# battery-nurse-1-2-1.net
KiCad netlist of a schematic drawn in EAGLE
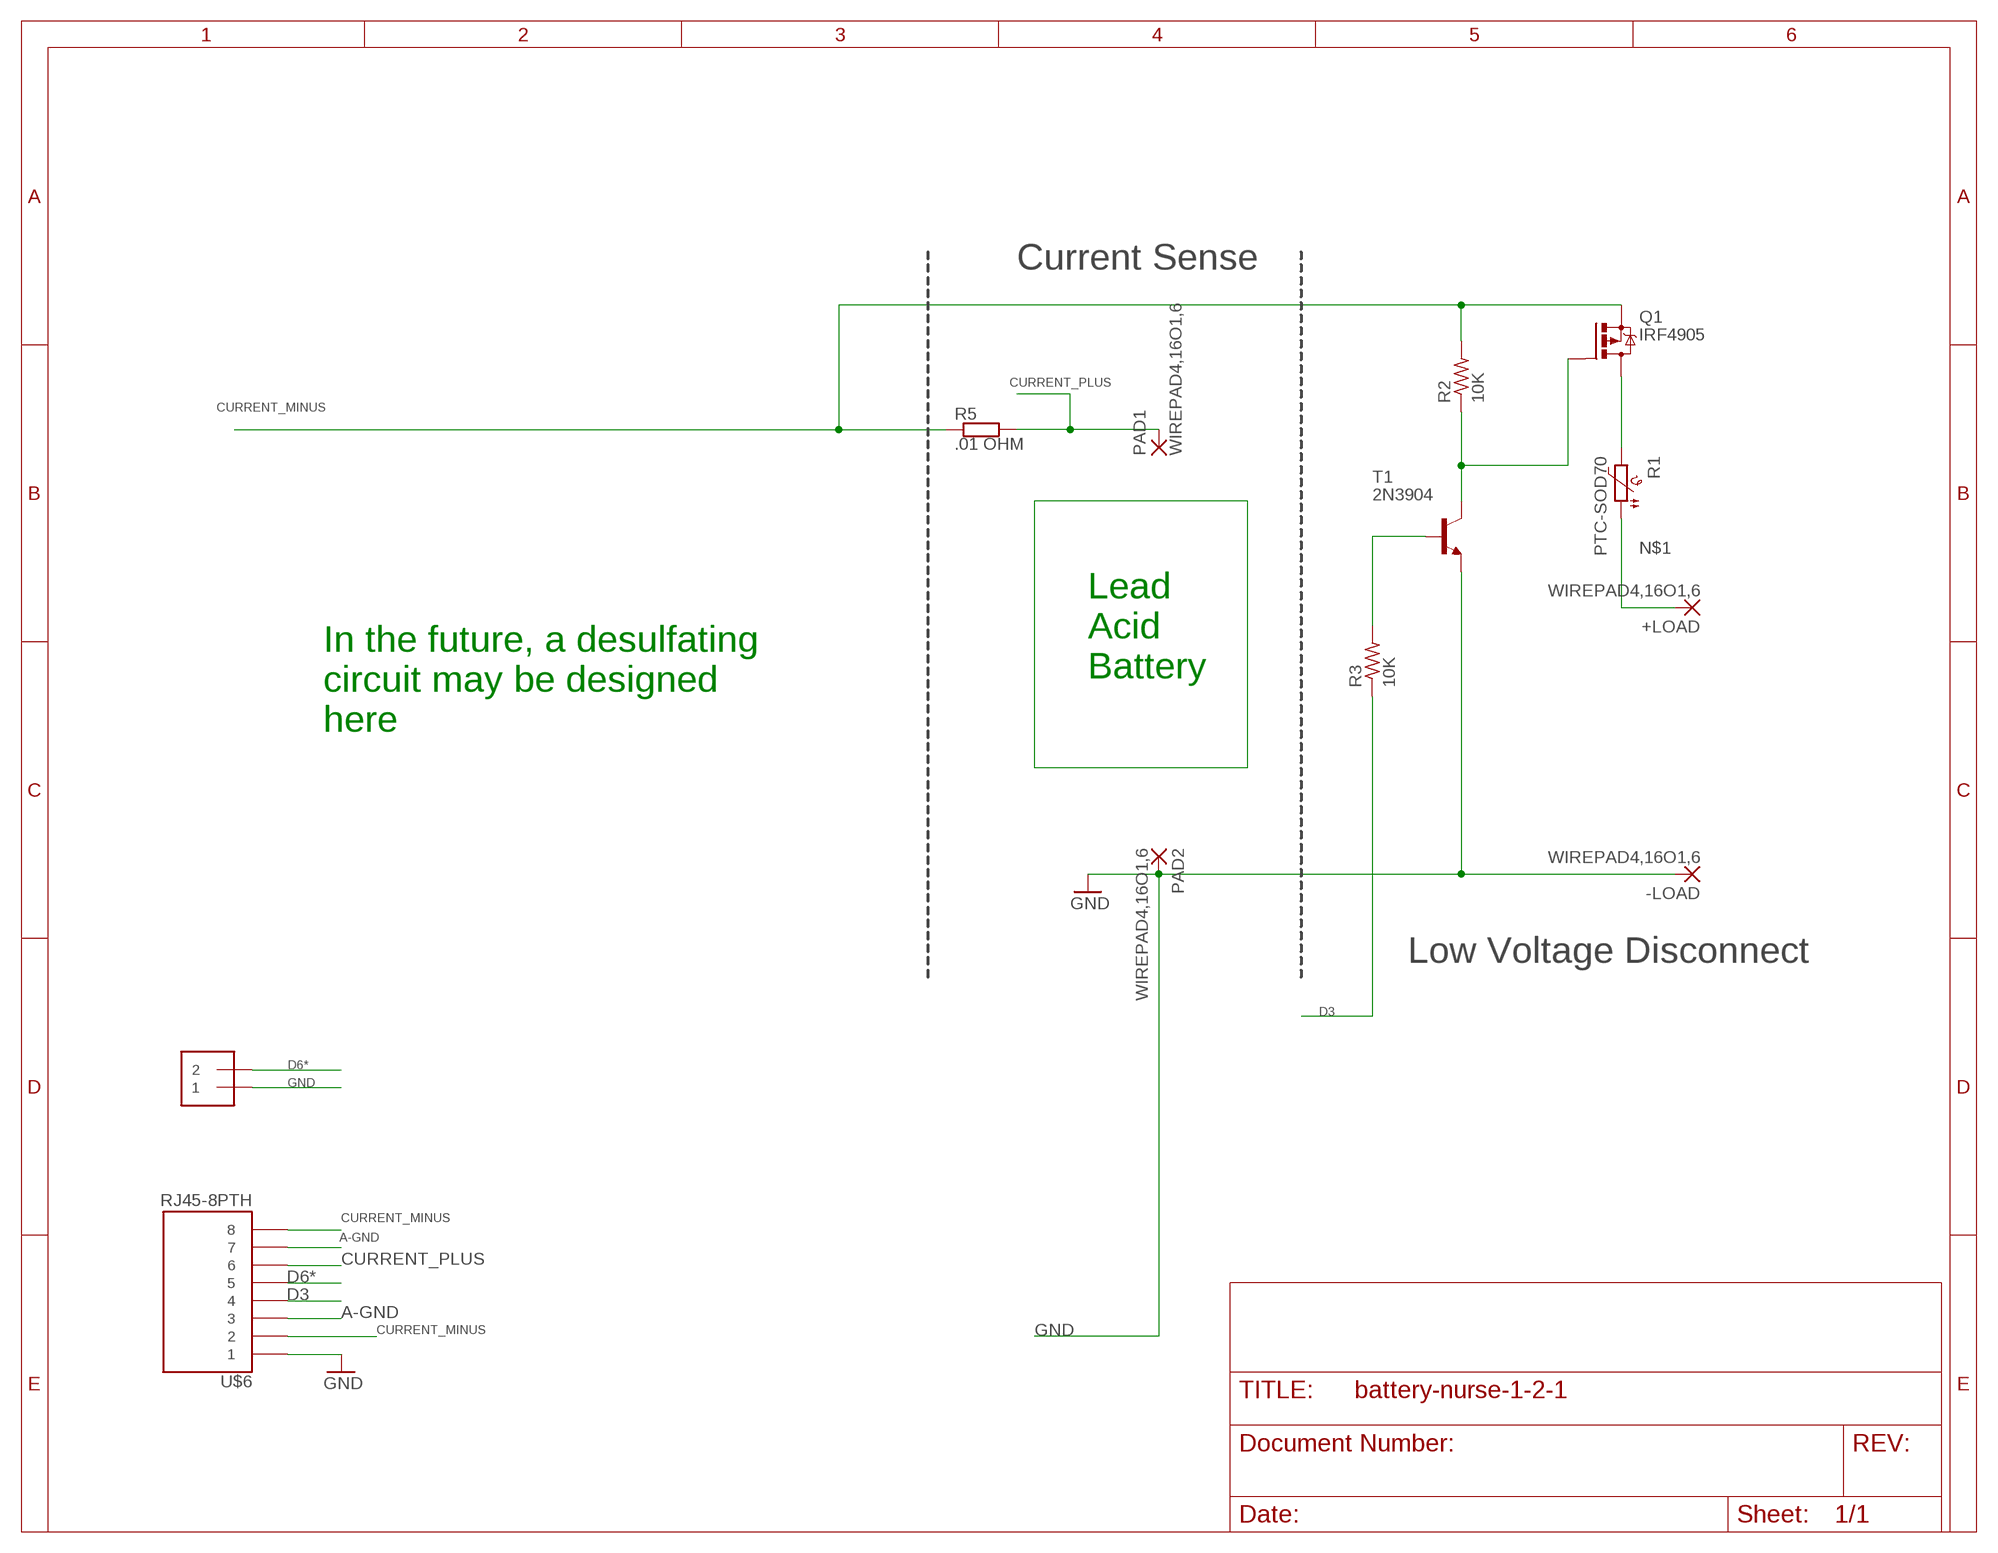
[diagram p0: schematic, sheet 1]

(export (version "E")
  (design (tool "Eeschema 10.0.6"))
  (components
    (comp (ref "+LOAD")
      (value "WIREPAD4,16O1,6")
      (footprint "eagle-import:4,16O1,6")
      (libsource (lib "eagle-import") (part "WIREPAD4,16O1,6"))
    )
    (comp (ref "-LOAD")
      (value "WIREPAD4,16O1,6")
      (footprint "eagle-import:4,16O1,6")
      (libsource (lib "eagle-import") (part "WIREPAD4,16O1,6"))
    )
    (comp (ref "J1")
      (value "1X2-3.5MM")
      (footprint "eagle-import:1X2-3.5MM")
      (libsource (lib "eagle-import") (part "1X2-3.5MM"))
    )
    (comp (ref "PAD1")
      (value "WIREPAD4,16O1,6")
      (footprint "eagle-import:4,16O1,6")
      (libsource (lib "eagle-import") (part "WIREPAD4,16O1,6"))
    )
    (comp (ref "PAD2")
      (value "WIREPAD4,16O1,6")
      (footprint "eagle-import:4,16O1,6")
      (libsource (lib "eagle-import") (part "WIREPAD4,16O1,6"))
    )
    (comp (ref "Q1")
      (value "IRF4905")
      (footprint "eagle-import:TO220BH")
      (libsource (lib "eagle-import") (part "IRF4905"))
    )
    (comp (ref "R1")
      (value "PTC-SOD70")
      (footprint "eagle-import:SOD70")
      (libsource (lib "eagle-import") (part "PTC-SOD70"))
    )
    (comp (ref "R2")
      (value "10K")
      (footprint "eagle-import:0204_7")
      (libsource (lib "eagle-import") (part "R-US_0204/7"))
    )
    (comp (ref "R3")
      (value "10K")
      (footprint "eagle-import:0204_7")
      (libsource (lib "eagle-import") (part "R-US_0204/7"))
    )
    (comp (ref "R5")
      (value ".01 OHM")
      (footprint "eagle-import:SMT-REF")
      (libsource (lib "eagle-import") (part "SMT-REF"))
    )
    (comp (ref "T1")
      (value "2N3904")
      (footprint "eagle-import:TO92-EBC-OVAL")
      (libsource (lib "eagle-import") (part "2N2222"))
    )
    (comp (ref "U$6")
      (value "RJ45-8PTH")
      (footprint "eagle-import:RJ45-8")
      (libsource (lib "eagle-import") (part "RJ45-8PTH"))
    )
  )
  (nets
    (net (code "1") (name "/A-GND") (class "Default")
      (node (ref "U$6") (pin "3") (pinfunction "3_3") (pintype "bidirectional"))
      (node (ref "U$6") (pin "7") (pinfunction "7_7") (pintype "bidirectional"))
    )
    (net (code "2") (name "/CURRENT_MINUS") (class "Default")
      (node (ref "Q1") (pin "S") (pinfunction "S_S") (pintype "passive"))
      (node (ref "R2") (pin "2") (pinfunction "2_2") (pintype "passive"))
      (node (ref "R5") (pin "2") (pinfunction "2_2") (pintype "passive"))
      (node (ref "U$6") (pin "2") (pinfunction "2_2") (pintype "bidirectional"))
      (node (ref "U$6") (pin "8") (pinfunction "8_8") (pintype "bidirectional"))
    )
    (net (code "3") (name "/CURRENT_PLUS") (class "Default")
      (node (ref "PAD1") (pin "1") (pinfunction "P_1") (pintype "passive"))
      (node (ref "R5") (pin "1") (pinfunction "1_1") (pintype "passive"))
      (node (ref "U$6") (pin "6") (pinfunction "6_6") (pintype "bidirectional"))
    )
    (net (code "4") (name "/D3") (class "Default")
      (node (ref "R3") (pin "1") (pinfunction "1_1") (pintype "passive"))
      (node (ref "U$6") (pin "4") (pinfunction "4_4") (pintype "bidirectional"))
    )
    (net (code "5") (name "/D6*") (class "Default")
      (node (ref "J1") (pin "2") (pinfunction "2_2") (pintype "passive"))
      (node (ref "U$6") (pin "5") (pinfunction "5_5") (pintype "bidirectional"))
    )
    (net (code "6") (name "/N$1") (class "Default")
      (node (ref "+LOAD") (pin "1") (pinfunction "P_1") (pintype "passive"))
      (node (ref "R1") (pin "1") (pinfunction "1_1") (pintype "passive"))
    )
    (net (code "7") (name "GND") (class "Default")
      (node (ref "-LOAD") (pin "1") (pinfunction "P_1") (pintype "passive"))
      (node (ref "J1") (pin "1") (pinfunction "1_1") (pintype "passive"))
      (node (ref "PAD2") (pin "1") (pinfunction "P_1") (pintype "passive"))
      (node (ref "T1") (pin "E") (pinfunction "E_E") (pintype "passive"))
      (node (ref "U$6") (pin "1") (pinfunction "1_1") (pintype "bidirectional"))
    )
    (net (code "8") (name "Net-(Q1-PadD)") (class "Default")
      (node (ref "Q1") (pin "D") (pinfunction "D_D") (pintype "passive"))
      (node (ref "R1") (pin "2") (pinfunction "2_2") (pintype "passive"))
    )
    (net (code "9") (name "Net-(Q1-PadG)") (class "Default")
      (node (ref "Q1") (pin "G") (pinfunction "G_G") (pintype "passive"))
      (node (ref "R2") (pin "1") (pinfunction "1_1") (pintype "passive"))
      (node (ref "T1") (pin "C") (pinfunction "C_C") (pintype "passive"))
    )
    (net (code "10") (name "Net-(R3-Pad2)") (class "Default")
      (node (ref "R3") (pin "2") (pinfunction "2_2") (pintype "passive"))
      (node (ref "T1") (pin "B") (pinfunction "B_B") (pintype "passive"))
    )
  )
)
